# WS2812-Breakout_v11.net
KiCad netlist of a schematic drawn in EAGLE
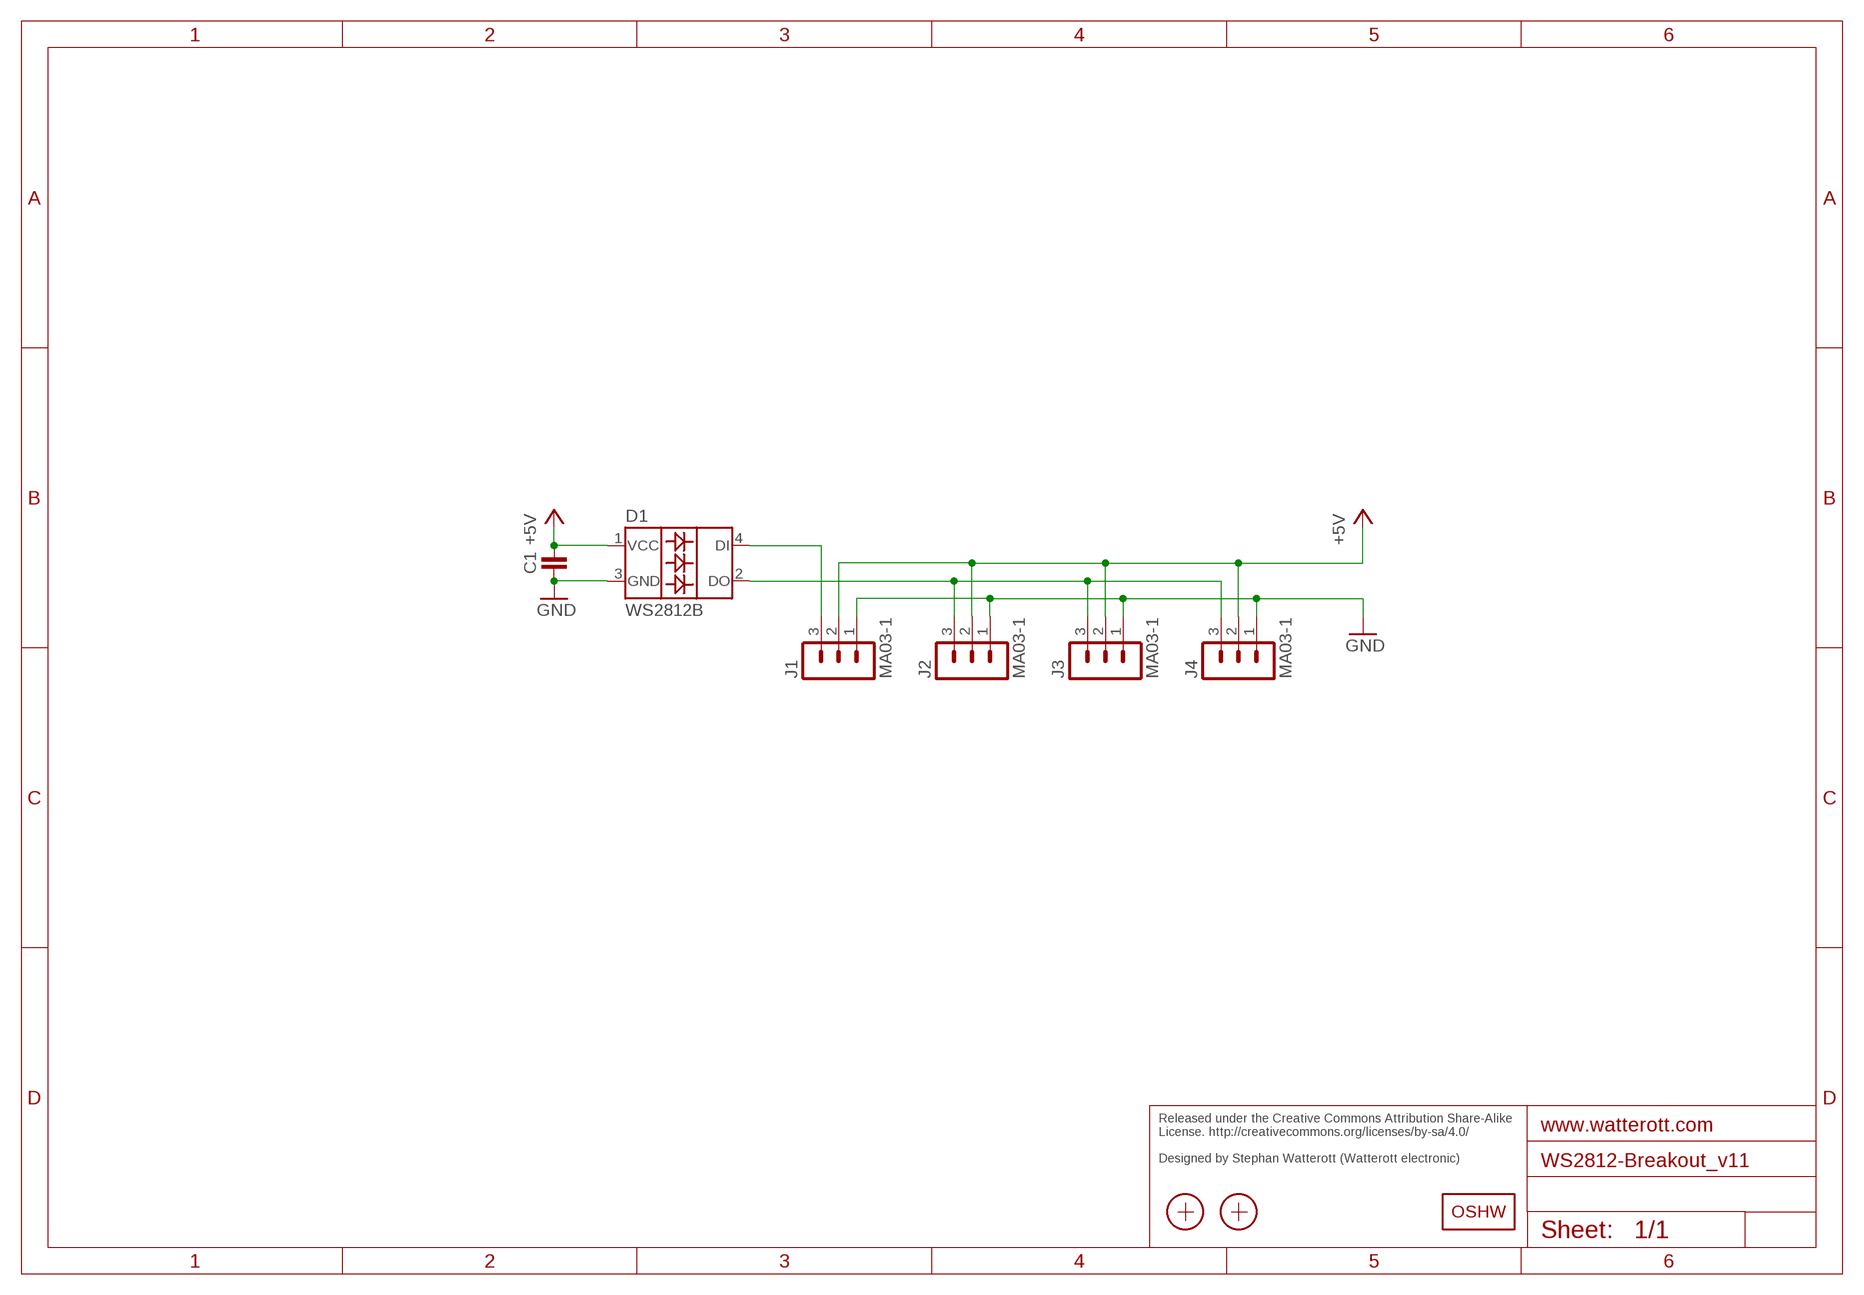
[diagram p0: schematic, sheet 1]

(export (version "E")
  (design (tool "Eeschema 10.0.6"))
  (components
    (comp (ref "C1")
      (value "CAPACITOR-0402")
      (footprint "eagle-import:C0402")
      (libsource (lib "eagle-import") (part "CAPACITOR-0402"))
    )
    (comp (ref "D1")
      (value "WS2812B")
      (footprint "eagle-import:WS2812B")
      (libsource (lib "eagle-import") (part "WS2812B"))
    )
    (comp (ref "J1")
      (value "MA03-1")
      (footprint "eagle-import:MA03-1")
      (libsource (lib "eagle-import") (part "MA03-1"))
    )
    (comp (ref "J2")
      (value "MA03-1")
      (footprint "eagle-import:MA03-1")
      (libsource (lib "eagle-import") (part "MA03-1"))
    )
    (comp (ref "J3")
      (value "MA03-1")
      (footprint "eagle-import:MA03-1")
      (libsource (lib "eagle-import") (part "MA03-1"))
    )
    (comp (ref "J4")
      (value "MA03-1")
      (footprint "eagle-import:MA03-1")
      (libsource (lib "eagle-import") (part "MA03-1"))
    )
    (comp (ref "LOGO1")
      (value "OSHW_LOGOX0070")
      (footprint "eagle-import:OSHW_6X70")
      (libsource (lib "eagle-import") (part "OSHW_LOGOX0070"))
    )
    (comp (ref "X1")
      (value "PASSER-07")
      (footprint "eagle-import:PASSER_07MM")
      (libsource (lib "eagle-import") (part "PASSER-07"))
    )
    (comp (ref "X2")
      (value "PASSER-07")
      (footprint "eagle-import:PASSER_07MM")
      (libsource (lib "eagle-import") (part "PASSER-07"))
    )
  )
  (nets
    (net (code "1") (name "+5V") (class "Default")
      (node (ref "C1") (pin "2") (pinfunction "2_2") (pintype "passive"))
      (node (ref "D1") (pin "1") (pinfunction "VCC_1") (pintype "power_in"))
      (node (ref "J1") (pin "2") (pinfunction "2_2") (pintype "passive"))
      (node (ref "J2") (pin "2") (pinfunction "2_2") (pintype "passive"))
      (node (ref "J3") (pin "2") (pinfunction "2_2") (pintype "passive"))
      (node (ref "J4") (pin "2") (pinfunction "2_2") (pintype "passive"))
    )
    (net (code "2") (name "GND") (class "Default")
      (node (ref "C1") (pin "1") (pinfunction "1_1") (pintype "passive"))
      (node (ref "D1") (pin "3") (pinfunction "GND_3") (pintype "power_in"))
      (node (ref "J1") (pin "1") (pinfunction "1_1") (pintype "passive"))
      (node (ref "J2") (pin "1") (pinfunction "1_1") (pintype "passive"))
      (node (ref "J3") (pin "1") (pinfunction "1_1") (pintype "passive"))
      (node (ref "J4") (pin "1") (pinfunction "1_1") (pintype "passive"))
    )
    (net (code "3") (name "Net-(D1-DI)") (class "Default")
      (node (ref "D1") (pin "4") (pinfunction "DI_4") (pintype "bidirectional"))
      (node (ref "J1") (pin "3") (pinfunction "3_3") (pintype "passive"))
    )
    (net (code "4") (name "Net-(D1-DO)") (class "Default")
      (node (ref "D1") (pin "2") (pinfunction "DO_2") (pintype "bidirectional"))
      (node (ref "J2") (pin "3") (pinfunction "3_3") (pintype "passive"))
      (node (ref "J3") (pin "3") (pinfunction "3_3") (pintype "passive"))
      (node (ref "J4") (pin "3") (pinfunction "3_3") (pintype "passive"))
    )
  )
)
